# contact_sensor.net
KiCad netlist of a schematic drawn in EAGLE
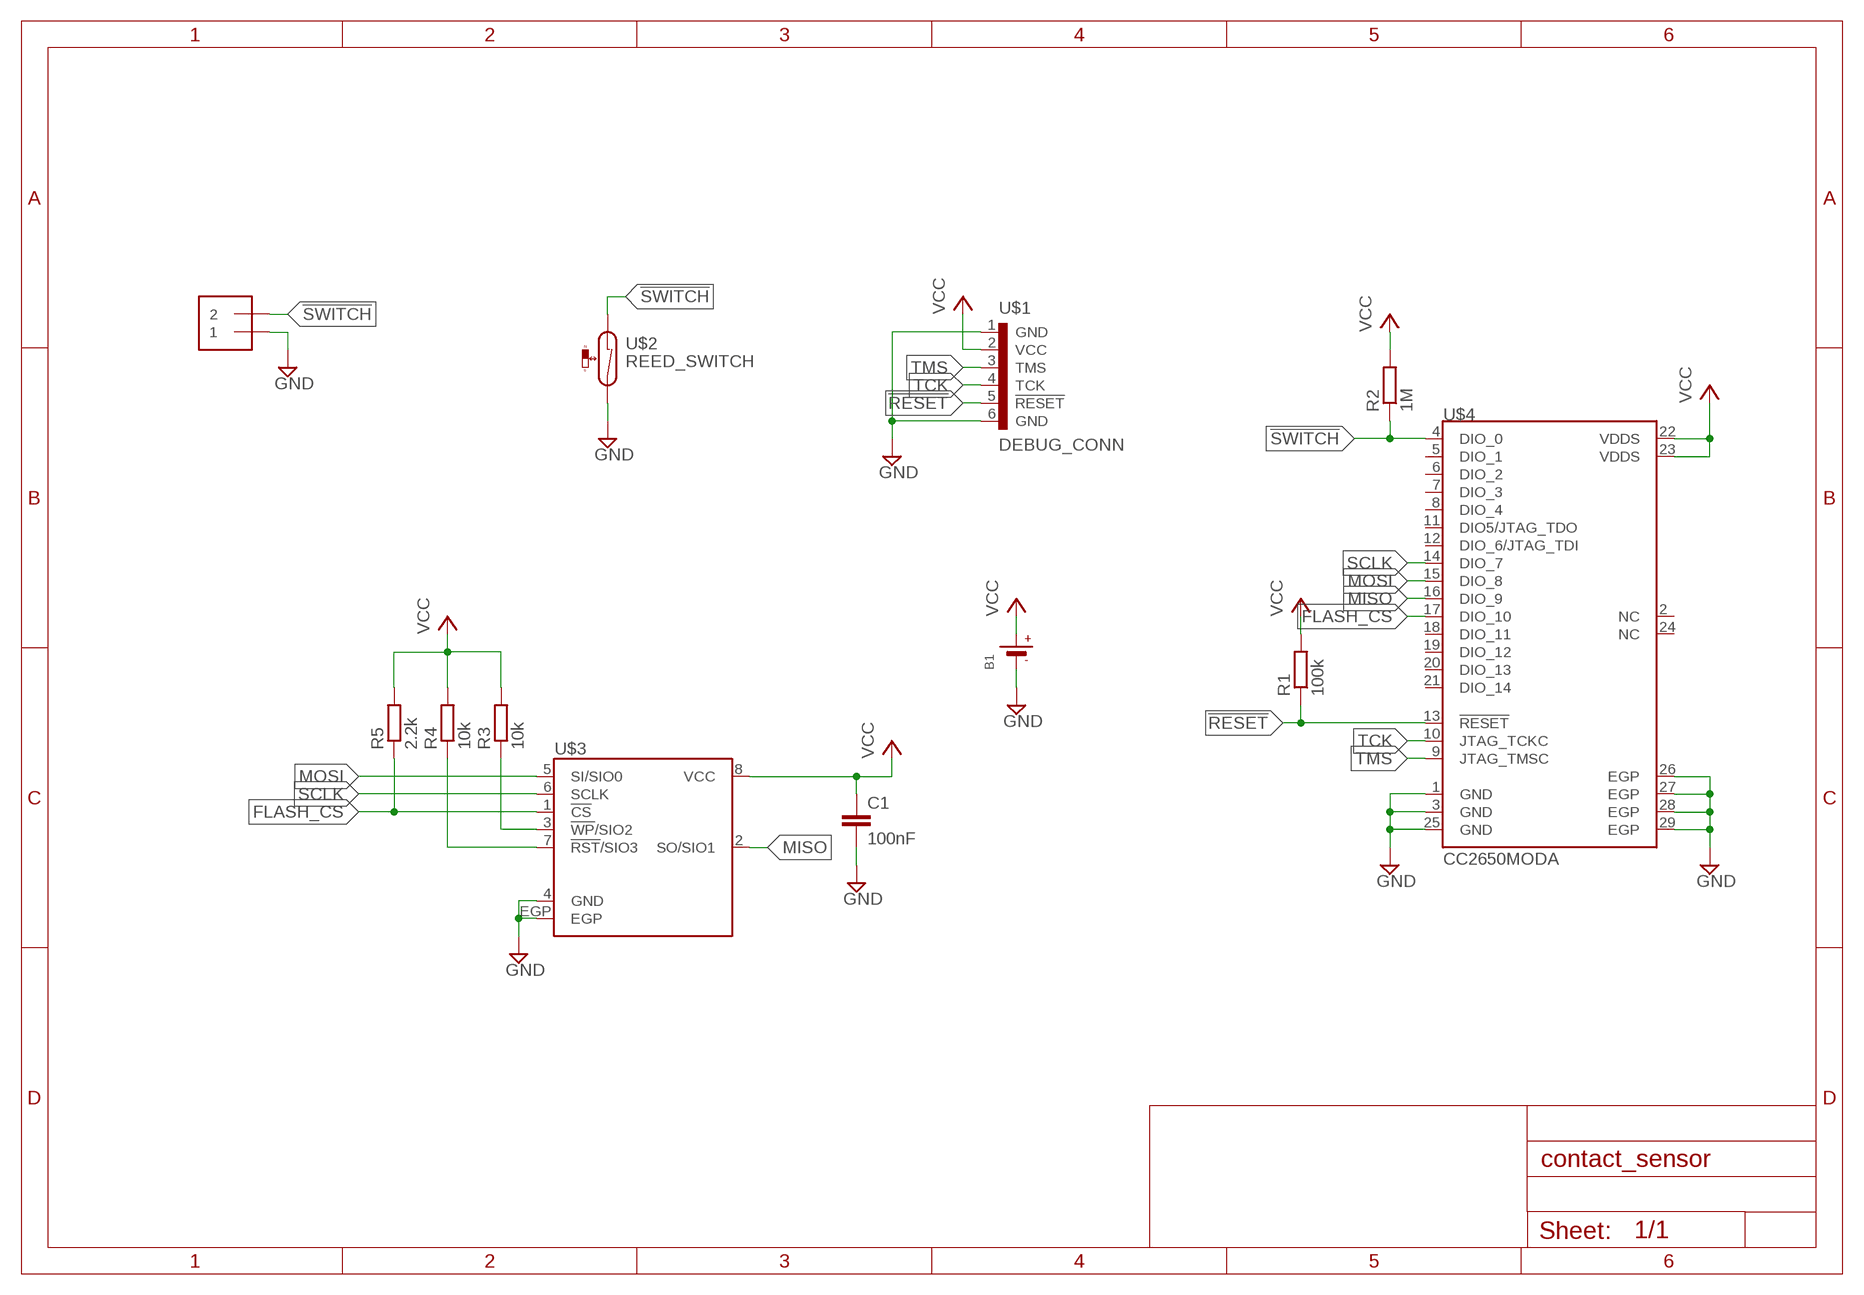
[diagram p0: schematic, sheet 1]

(export (version "E")
  (design (tool "Eeschema 10.0.6"))
  (components
    (comp (ref "B1")
      (value "BATTERYCR2032_BAT-HLD-001")
      (footprint "eagle-import:CR2032_SMT_BAT-HLD-001")
      (libsource (lib "eagle-import") (part "BATTERYCR2032_BAT-HLD-001"))
    )
    (comp (ref "C1")
      (value "100nF")
      (footprint "eagle-import:0402")
      (libsource (lib "eagle-import") (part "CAPACITOR_0402"))
    )
    (comp (ref "J2")
      (value "1X2-3.5MM")
      (footprint "eagle-import:1X2-3.5MM")
      (libsource (lib "eagle-import") (part "1X2-3.5MM"))
    )
    (comp (ref "R1")
      (value "100k")
      (footprint "eagle-import:0402")
      (libsource (lib "eagle-import") (part "RESISTOR_0402"))
    )
    (comp (ref "R2")
      (value "1M")
      (footprint "eagle-import:0402")
      (libsource (lib "eagle-import") (part "RESISTOR_0402"))
    )
    (comp (ref "R3")
      (value "10k")
      (footprint "eagle-import:0402")
      (libsource (lib "eagle-import") (part "RESISTOR_0402"))
    )
    (comp (ref "R4")
      (value "10k")
      (footprint "eagle-import:0402")
      (libsource (lib "eagle-import") (part "RESISTOR_0402"))
    )
    (comp (ref "R5")
      (value "2.2k")
      (footprint "eagle-import:0402")
      (libsource (lib "eagle-import") (part "RESISTOR_0402"))
    )
    (comp (ref "U$1")
      (value "DEBUG_CONN")
      (footprint "eagle-import:DEBUG_CONN")
      (libsource (lib "eagle-import") (part "DEBUG_CONN"))
    )
    (comp (ref "U$2")
      (value "REED_SWITCH")
      (footprint "eagle-import:REED_SWITCH")
      (libsource (lib "eagle-import") (part "REED_SWITCH"))
    )
    (comp (ref "U$3")
      (value "MX25R8035FMX25R8035FZUIL0")
      (footprint "eagle-import:MX25R8035FZUIL0")
      (libsource (lib "eagle-import") (part "MX25R8035FMX25R8035FZUIL0"))
    )
    (comp (ref "U$4")
      (value "CC2650MODA")
      (footprint "eagle-import:CC2650MODA")
      (libsource (lib "eagle-import") (part "CC2650MODA"))
    )
  )
  (nets
    (net (code "1") (name "/~{RESET}") (class "Default")
      (node (ref "R1") (pin "1") (pinfunction "1_1") (pintype "passive"))
      (node (ref "U$1") (pin "5") (pinfunction "~{RESET}_5") (pintype "bidirectional"))
      (node (ref "U$4") (pin "13") (pinfunction "~{RESET}_13") (pintype "bidirectional"))
    )
    (net (code "2") (name "/~{SWITCH}") (class "Default")
      (node (ref "J2") (pin "2") (pinfunction "2_2") (pintype "passive"))
      (node (ref "R2") (pin "1") (pinfunction "1_1") (pintype "passive"))
      (node (ref "U$2") (pin "1") (pinfunction "1_1") (pintype "passive"))
      (node (ref "U$4") (pin "4") (pinfunction "DIO_0_4") (pintype "bidirectional"))
    )
    (net (code "3") (name "FLASH_CS") (class "Default")
      (node (ref "R5") (pin "1") (pinfunction "1_1") (pintype "passive"))
      (node (ref "U$3") (pin "1") (pinfunction "~{CS}_1") (pintype "input"))
      (node (ref "U$4") (pin "17") (pinfunction "DIO_10_17") (pintype "bidirectional"))
    )
    (net (code "4") (name "GND") (class "Default")
      (node (ref "B1") (pin "-") (pinfunction "-_-") (pintype "passive"))
      (node (ref "C1") (pin "2") (pinfunction "2_2") (pintype "passive"))
      (node (ref "J2") (pin "1") (pinfunction "1_1") (pintype "passive"))
      (node (ref "U$1") (pin "1") (pinfunction "GND_1") (pintype "bidirectional"))
      (node (ref "U$1") (pin "6") (pinfunction "GND_6") (pintype "bidirectional"))
      (node (ref "U$2") (pin "2") (pinfunction "2_2") (pintype "passive"))
      (node (ref "U$3") (pin "4") (pinfunction "GND_4") (pintype "power_in"))
      (node (ref "U$3") (pin "EGP") (pinfunction "EGP_EGP") (pintype "power_in"))
      (node (ref "U$4") (pin "1") (pinfunction "GND_1") (pintype "power_in"))
      (node (ref "U$4") (pin "25") (pinfunction "GND_25") (pintype "power_in"))
      (node (ref "U$4") (pin "26") (pinfunction "EGP_26") (pintype "power_in"))
      (node (ref "U$4") (pin "27") (pinfunction "EGP_27") (pintype "power_in"))
      (node (ref "U$4") (pin "28") (pinfunction "EGP_28") (pintype "power_in"))
      (node (ref "U$4") (pin "29") (pinfunction "EGP_29") (pintype "power_in"))
      (node (ref "U$4") (pin "3") (pinfunction "GND_3") (pintype "power_in"))
    )
    (net (code "5") (name "MISO") (class "Default")
      (node (ref "U$3") (pin "2") (pinfunction "SO/SIO1_2") (pintype "bidirectional"))
      (node (ref "U$4") (pin "16") (pinfunction "DIO_9_16") (pintype "bidirectional"))
    )
    (net (code "6") (name "MOSI") (class "Default")
      (node (ref "U$3") (pin "5") (pinfunction "SI/SIO0_5") (pintype "bidirectional"))
      (node (ref "U$4") (pin "15") (pinfunction "DIO_8_15") (pintype "bidirectional"))
    )
    (net (code "7") (name "Net-(U$3-~{RST}{slash}SIO3)") (class "Default")
      (node (ref "R4") (pin "1") (pinfunction "1_1") (pintype "passive"))
      (node (ref "U$3") (pin "7") (pinfunction "~{RST}/SIO3_7") (pintype "bidirectional"))
    )
    (net (code "8") (name "Net-(U$3-~{WP}{slash}SIO2)") (class "Default")
      (node (ref "R3") (pin "1") (pinfunction "1_1") (pintype "passive"))
      (node (ref "U$3") (pin "3") (pinfunction "~{WP}/SIO2_3") (pintype "bidirectional"))
    )
    (net (code "9") (name "SCLK") (class "Default")
      (node (ref "U$3") (pin "6") (pinfunction "SCLK_6") (pintype "input"))
      (node (ref "U$4") (pin "14") (pinfunction "DIO_7_14") (pintype "bidirectional"))
    )
    (net (code "10") (name "TCK") (class "Default")
      (node (ref "U$1") (pin "4") (pinfunction "TCK_4") (pintype "bidirectional"))
      (node (ref "U$4") (pin "10") (pinfunction "JTAG_TCKC_10") (pintype "bidirectional"))
    )
    (net (code "11") (name "TMS") (class "Default")
      (node (ref "U$1") (pin "3") (pinfunction "TMS_3") (pintype "bidirectional"))
      (node (ref "U$4") (pin "9") (pinfunction "JTAG_TMSC_9") (pintype "bidirectional"))
    )
    (net (code "12") (name "VCC") (class "Default")
      (node (ref "B1") (pin "+$1") (pinfunction "+_+$1") (pintype "passive"))
      (node (ref "B1") (pin "+$2") (pinfunction "+_+$2") (pintype "passive"))
      (node (ref "C1") (pin "1") (pinfunction "1_1") (pintype "passive"))
      (node (ref "R1") (pin "2") (pinfunction "2_2") (pintype "passive"))
      (node (ref "R2") (pin "2") (pinfunction "2_2") (pintype "passive"))
      (node (ref "R3") (pin "2") (pinfunction "2_2") (pintype "passive"))
      (node (ref "R4") (pin "2") (pinfunction "2_2") (pintype "passive"))
      (node (ref "R5") (pin "2") (pinfunction "2_2") (pintype "passive"))
      (node (ref "U$1") (pin "2") (pinfunction "VCC_2") (pintype "bidirectional"))
      (node (ref "U$3") (pin "8") (pinfunction "VCC_8") (pintype "power_in"))
      (node (ref "U$4") (pin "22") (pinfunction "VDDS_22") (pintype "power_in"))
      (node (ref "U$4") (pin "23") (pinfunction "VDDS_23") (pintype "power_in"))
    )
    (net (code "13") (name "unconnected-(U$4-DIO5{slash}JTAG_TDO-Pad11)") (class "Default")
      (node (ref "U$4") (pin "11") (pinfunction "DIO5/JTAG_TDO_11") (pintype "bidirectional"))
    )
    (net (code "14") (name "unconnected-(U$4-DIO_1-Pad5)") (class "Default")
      (node (ref "U$4") (pin "5") (pinfunction "DIO_1_5") (pintype "bidirectional"))
    )
    (net (code "15") (name "unconnected-(U$4-DIO_2-Pad6)") (class "Default")
      (node (ref "U$4") (pin "6") (pinfunction "DIO_2_6") (pintype "bidirectional"))
    )
    (net (code "16") (name "unconnected-(U$4-DIO_3-Pad7)") (class "Default")
      (node (ref "U$4") (pin "7") (pinfunction "DIO_3_7") (pintype "bidirectional"))
    )
    (net (code "17") (name "unconnected-(U$4-DIO_4-Pad8)") (class "Default")
      (node (ref "U$4") (pin "8") (pinfunction "DIO_4_8") (pintype "bidirectional"))
    )
    (net (code "18") (name "unconnected-(U$4-DIO_6{slash}JTAG_TDI-Pad12)") (class "Default")
      (node (ref "U$4") (pin "12") (pinfunction "DIO_6/JTAG_TDI_12") (pintype "bidirectional"))
    )
    (net (code "19") (name "unconnected-(U$4-DIO_11-Pad18)") (class "Default")
      (node (ref "U$4") (pin "18") (pinfunction "DIO_11_18") (pintype "bidirectional"))
    )
    (net (code "20") (name "unconnected-(U$4-DIO_12-Pad19)") (class "Default")
      (node (ref "U$4") (pin "19") (pinfunction "DIO_12_19") (pintype "bidirectional"))
    )
    (net (code "21") (name "unconnected-(U$4-DIO_13-Pad20)") (class "Default")
      (node (ref "U$4") (pin "20") (pinfunction "DIO_13_20") (pintype "bidirectional"))
    )
    (net (code "22") (name "unconnected-(U$4-DIO_14-Pad21)") (class "Default")
      (node (ref "U$4") (pin "21") (pinfunction "DIO_14_21") (pintype "bidirectional"))
    )
    (net (code "23") (name "unconnected-(U$4-NC-Pad2)") (class "Default")
      (node (ref "U$4") (pin "2") (pinfunction "NC_2") (pintype "no_connect"))
    )
    (net (code "24") (name "unconnected-(U$4-NC-Pad24)") (class "Default")
      (node (ref "U$4") (pin "24") (pinfunction "NC_24") (pintype "no_connect"))
    )
  )
)
